# Blown_Fuse_LED.net
KiCad netlist of a schematic drawn in Altium Designer
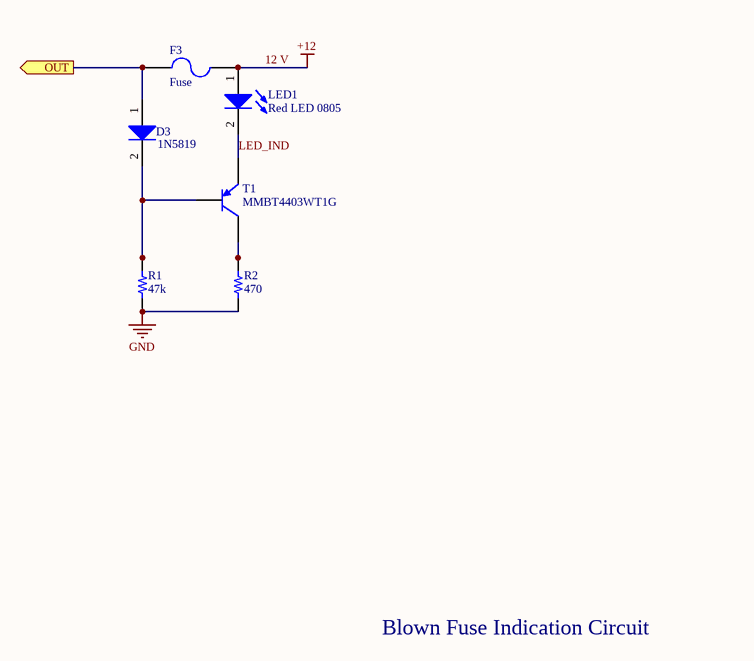
[diagram p0: Blown_Fuse_LED.SchDoc]

(export (version "E")
  (design (tool "Eeschema 10.0.6"))
  (components
    (comp (ref "D3")
      (value "1N5819")
      (footprint "SOD123F")
      (description "Diode Super Barrier 40V 1A Surface Mount SOD-123F")
      (fields (field (name "POWER") "40V") (field (name "MFRPARTNO") "1N5819HW1-7-F"))
      (libsource (lib "Altium-Lib") (part "DIODE"))
    )
    (comp (ref "F3")
      (value "Fuse")
      (footprint "3568-MiniFuseHolder")
      (libsource (lib "Altium-Lib") (part "Fuse"))
    )
    (comp (ref "LED1")
      (value "Red LED 0805")
      (footprint "0805_LED")
      (libsource (lib "Altium-Lib") (part "LED"))
    )
    (comp (ref "R1")
      (value "47k")
      (footprint "RES 0805/2012")
      (fields
        (field (name "TOLERANCE") "1%")
        (field (name "POWER") "1/10W")
        (field (name "Comment") "Resistor 47k 0805 1/10W 1%")
        (field (name "CREATED_BY") "Nick Mah")
      )
      (libsource (lib "Altium-Lib") (part "Resistor"))
    )
    (comp (ref "R2")
      (value "470")
      (footprint "RES 0805/2012")
      (fields
        (field (name "TOLERANCE") "1%")
        (field (name "POWER") "1/10W")
        (field (name "Comment") "Resistor 470 0805 1/10W 1%")
        (field (name "CREATED_BY") "Nick Mah")
      )
      (libsource (lib "Altium-Lib") (part "Resistor"))
    )
    (comp (ref "T1")
      (value "MMBT4403WT1G")
      (footprint "SOT23-3")
      (fields (field (name "CREATED_BY") "Angel"))
      (libsource (lib "Altium-Lib") (part "PNP Transistor"))
    )
  )
  (nets
    (net (code "1") (name "+12") (class "Default")
      (node (ref "F3") (pin "2") (pinfunction "2_2") (pintype "passive"))
      (node (ref "LED1") (pin "1") (pinfunction "A_1") (pintype "passive"))
    )
    (net (code "2") (name "/LED_IND") (class "Default")
      (node (ref "LED1") (pin "2") (pinfunction "K_2") (pintype "passive"))
      (node (ref "T1") (pin "2") (pinfunction "E_2") (pintype "passive"))
    )
    (net (code "3") (name "/OUT") (class "Default")
      (node (ref "D3") (pin "1") (pinfunction "A_1") (pintype "passive"))
      (node (ref "F3") (pin "1") (pinfunction "1_1") (pintype "passive"))
    )
    (net (code "4") (name "GND") (class "Default")
      (node (ref "R1") (pin "2") (pinfunction "2_2") (pintype "passive"))
      (node (ref "R2") (pin "2") (pinfunction "2_2") (pintype "passive"))
    )
    (net (code "5") (name "Net-(D3-K)") (class "Default")
      (node (ref "D3") (pin "2") (pinfunction "K_2") (pintype "passive"))
      (node (ref "R1") (pin "1") (pinfunction "1_1") (pintype "passive"))
      (node (ref "T1") (pin "1") (pinfunction "B_1") (pintype "passive"))
    )
    (net (code "6") (name "Net-(T1-C)") (class "Default")
      (node (ref "R2") (pin "1") (pinfunction "1_1") (pintype "passive"))
      (node (ref "T1") (pin "3") (pinfunction "C_3") (pintype "passive"))
    )
  )
)
